# Boje.net
KiCad netlist of a schematic drawn in EAGLE
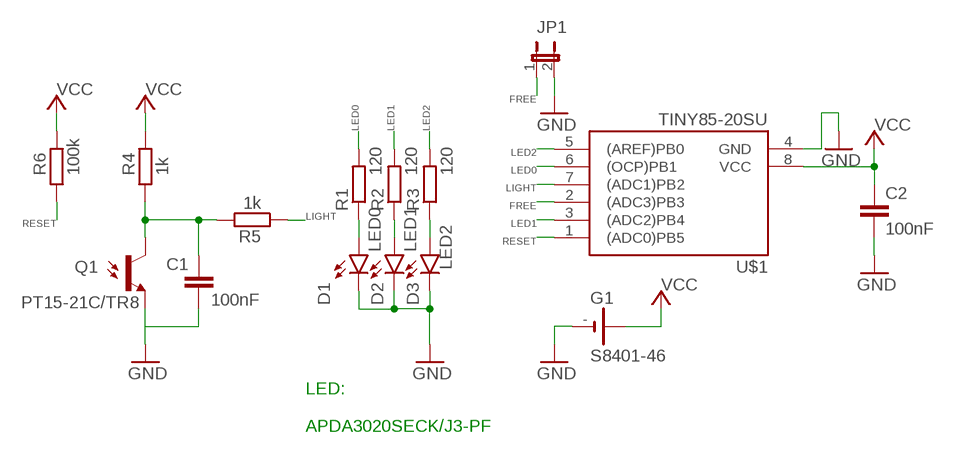
[diagram p0: schematic, sheet 1]

(export (version "E")
  (design (tool "Eeschema 10.0.6"))
  (components
    (comp (ref "C1")
      (value "100nF")
      (footprint "eagle-import:C0603")
      (libsource (lib "eagle-import") (part "C-EUC0603"))
    )
    (comp (ref "C2")
      (value "100nF")
      (footprint "eagle-import:C0603")
      (libsource (lib "eagle-import") (part "C-EUC0603"))
    )
    (comp (ref "D1")
      (value "LED0")
      (footprint "eagle-import:LED5MM")
      (libsource (lib "eagle-import") (part "LED5MM"))
    )
    (comp (ref "D2")
      (value "LED1")
      (footprint "eagle-import:LED5MM")
      (libsource (lib "eagle-import") (part "LED5MM"))
    )
    (comp (ref "D3")
      (value "LED2")
      (footprint "eagle-import:LED5MM")
      (libsource (lib "eagle-import") (part "LED5MM"))
    )
    (comp (ref "G1")
      (value "S8401-46")
      (footprint "eagle-import:CR2032V")
      (libsource (lib "eagle-import") (part "CR2032V"))
    )
    (comp (ref "JP1")
      (value "JP1E")
      (footprint "eagle-import:JP1")
      (libsource (lib "eagle-import") (part "JP1E"))
    )
    (comp (ref "Q1")
      (value "PT15-21C/TR8")
      (footprint "eagle-import:PT17-21C-L41-TR8")
      (libsource (lib "eagle-import") (part "PHOTOTRANSISTORPT17-21C-L41-TR8"))
    )
    (comp (ref "R1")
      (value "120")
      (footprint "eagle-import:R0603")
      (libsource (lib "eagle-import") (part "R-EU_R0603"))
    )
    (comp (ref "R2")
      (value "120")
      (footprint "eagle-import:R0603")
      (libsource (lib "eagle-import") (part "R-EU_R0603"))
    )
    (comp (ref "R3")
      (value "120")
      (footprint "eagle-import:R0603")
      (libsource (lib "eagle-import") (part "R-EU_R0603"))
    )
    (comp (ref "R4")
      (value "1k")
      (footprint "eagle-import:R0603")
      (libsource (lib "eagle-import") (part "R-EU_R0603"))
    )
    (comp (ref "R5")
      (value "1k")
      (footprint "eagle-import:R0603")
      (libsource (lib "eagle-import") (part "R-EU_R0603"))
    )
    (comp (ref "R6")
      (value "100k")
      (footprint "eagle-import:R0603")
      (libsource (lib "eagle-import") (part "R-EU_R0603"))
    )
    (comp (ref "U$1")
      (value "TINY85-20SU")
      (footprint "eagle-import:SOIC8")
      (libsource (lib "eagle-import") (part "TINY25/45/85-20SU"))
    )
  )
  (nets
    (net (code "1") (name "/FREE") (class "Default")
      (node (ref "JP1") (pin "1") (pinfunction "1_1") (pintype "passive"))
      (node (ref "U$1") (pin "2") (pinfunction "(ADC3)PB3_2") (pintype "bidirectional"))
    )
    (net (code "2") (name "/LED0") (class "Default")
      (node (ref "R1") (pin "2") (pinfunction "2_2") (pintype "passive"))
      (node (ref "U$1") (pin "6") (pinfunction "(OCP)PB1_6") (pintype "bidirectional"))
    )
    (net (code "3") (name "/LED1") (class "Default")
      (node (ref "R2") (pin "2") (pinfunction "2_2") (pintype "passive"))
      (node (ref "U$1") (pin "3") (pinfunction "(ADC2)PB4_3") (pintype "bidirectional"))
    )
    (net (code "4") (name "/LED2") (class "Default")
      (node (ref "R3") (pin "2") (pinfunction "2_2") (pintype "passive"))
      (node (ref "U$1") (pin "5") (pinfunction "(AREF)PB0_5") (pintype "bidirectional"))
    )
    (net (code "5") (name "/LIGHT") (class "Default")
      (node (ref "R5") (pin "1") (pinfunction "1_1") (pintype "passive"))
      (node (ref "U$1") (pin "7") (pinfunction "(ADC1)PB2_7") (pintype "bidirectional"))
    )
    (net (code "6") (name "/RESET") (class "Default")
      (node (ref "R6") (pin "1") (pinfunction "1_1") (pintype "passive"))
      (node (ref "U$1") (pin "1") (pinfunction "(ADC0)PB5_1") (pintype "bidirectional"))
    )
    (net (code "7") (name "GND") (class "Default")
      (node (ref "C1") (pin "1") (pinfunction "1_1") (pintype "passive"))
      (node (ref "C2") (pin "2") (pinfunction "2_2") (pintype "passive"))
      (node (ref "D1") (pin "K") (pinfunction "C_K") (pintype "passive"))
      (node (ref "D2") (pin "K") (pinfunction "C_K") (pintype "passive"))
      (node (ref "D3") (pin "K") (pinfunction "C_K") (pintype "passive"))
      (node (ref "G1") (pin "-") (pinfunction "-_-") (pintype "passive"))
      (node (ref "JP1") (pin "2") (pinfunction "2_2") (pintype "passive"))
      (node (ref "Q1") (pin "E") (pinfunction "E_E") (pintype "passive"))
      (node (ref "U$1") (pin "4") (pinfunction "GND_4") (pintype "power_in"))
    )
    (net (code "8") (name "Net-(C1-Pad2)") (class "Default")
      (node (ref "C1") (pin "2") (pinfunction "2_2") (pintype "passive"))
      (node (ref "Q1") (pin "C") (pinfunction "C_C") (pintype "passive"))
      (node (ref "R4") (pin "1") (pinfunction "1_1") (pintype "passive"))
      (node (ref "R5") (pin "2") (pinfunction "2_2") (pintype "passive"))
    )
    (net (code "9") (name "Net-(D1-PadA)") (class "Default")
      (node (ref "D1") (pin "A") (pinfunction "A_A") (pintype "passive"))
      (node (ref "R1") (pin "1") (pinfunction "1_1") (pintype "passive"))
    )
    (net (code "10") (name "Net-(D2-PadA)") (class "Default")
      (node (ref "D2") (pin "A") (pinfunction "A_A") (pintype "passive"))
      (node (ref "R2") (pin "1") (pinfunction "1_1") (pintype "passive"))
    )
    (net (code "11") (name "Net-(D3-PadA)") (class "Default")
      (node (ref "D3") (pin "A") (pinfunction "A_A") (pintype "passive"))
      (node (ref "R3") (pin "1") (pinfunction "1_1") (pintype "passive"))
    )
    (net (code "12") (name "VCC") (class "Default")
      (node (ref "C2") (pin "1") (pinfunction "1_1") (pintype "passive"))
      (node (ref "G1") (pin "+0") (pinfunction "+_+0") (pintype "passive"))
      (node (ref "G1") (pin "+1") (pinfunction "+_+1") (pintype "passive"))
      (node (ref "R4") (pin "2") (pinfunction "2_2") (pintype "passive"))
      (node (ref "R6") (pin "2") (pinfunction "2_2") (pintype "passive"))
      (node (ref "U$1") (pin "8") (pinfunction "VCC_8") (pintype "power_in"))
    )
  )
)
